# LM5177_PINOUT.net
KiCad netlist of a schematic drawn in Altium Designer
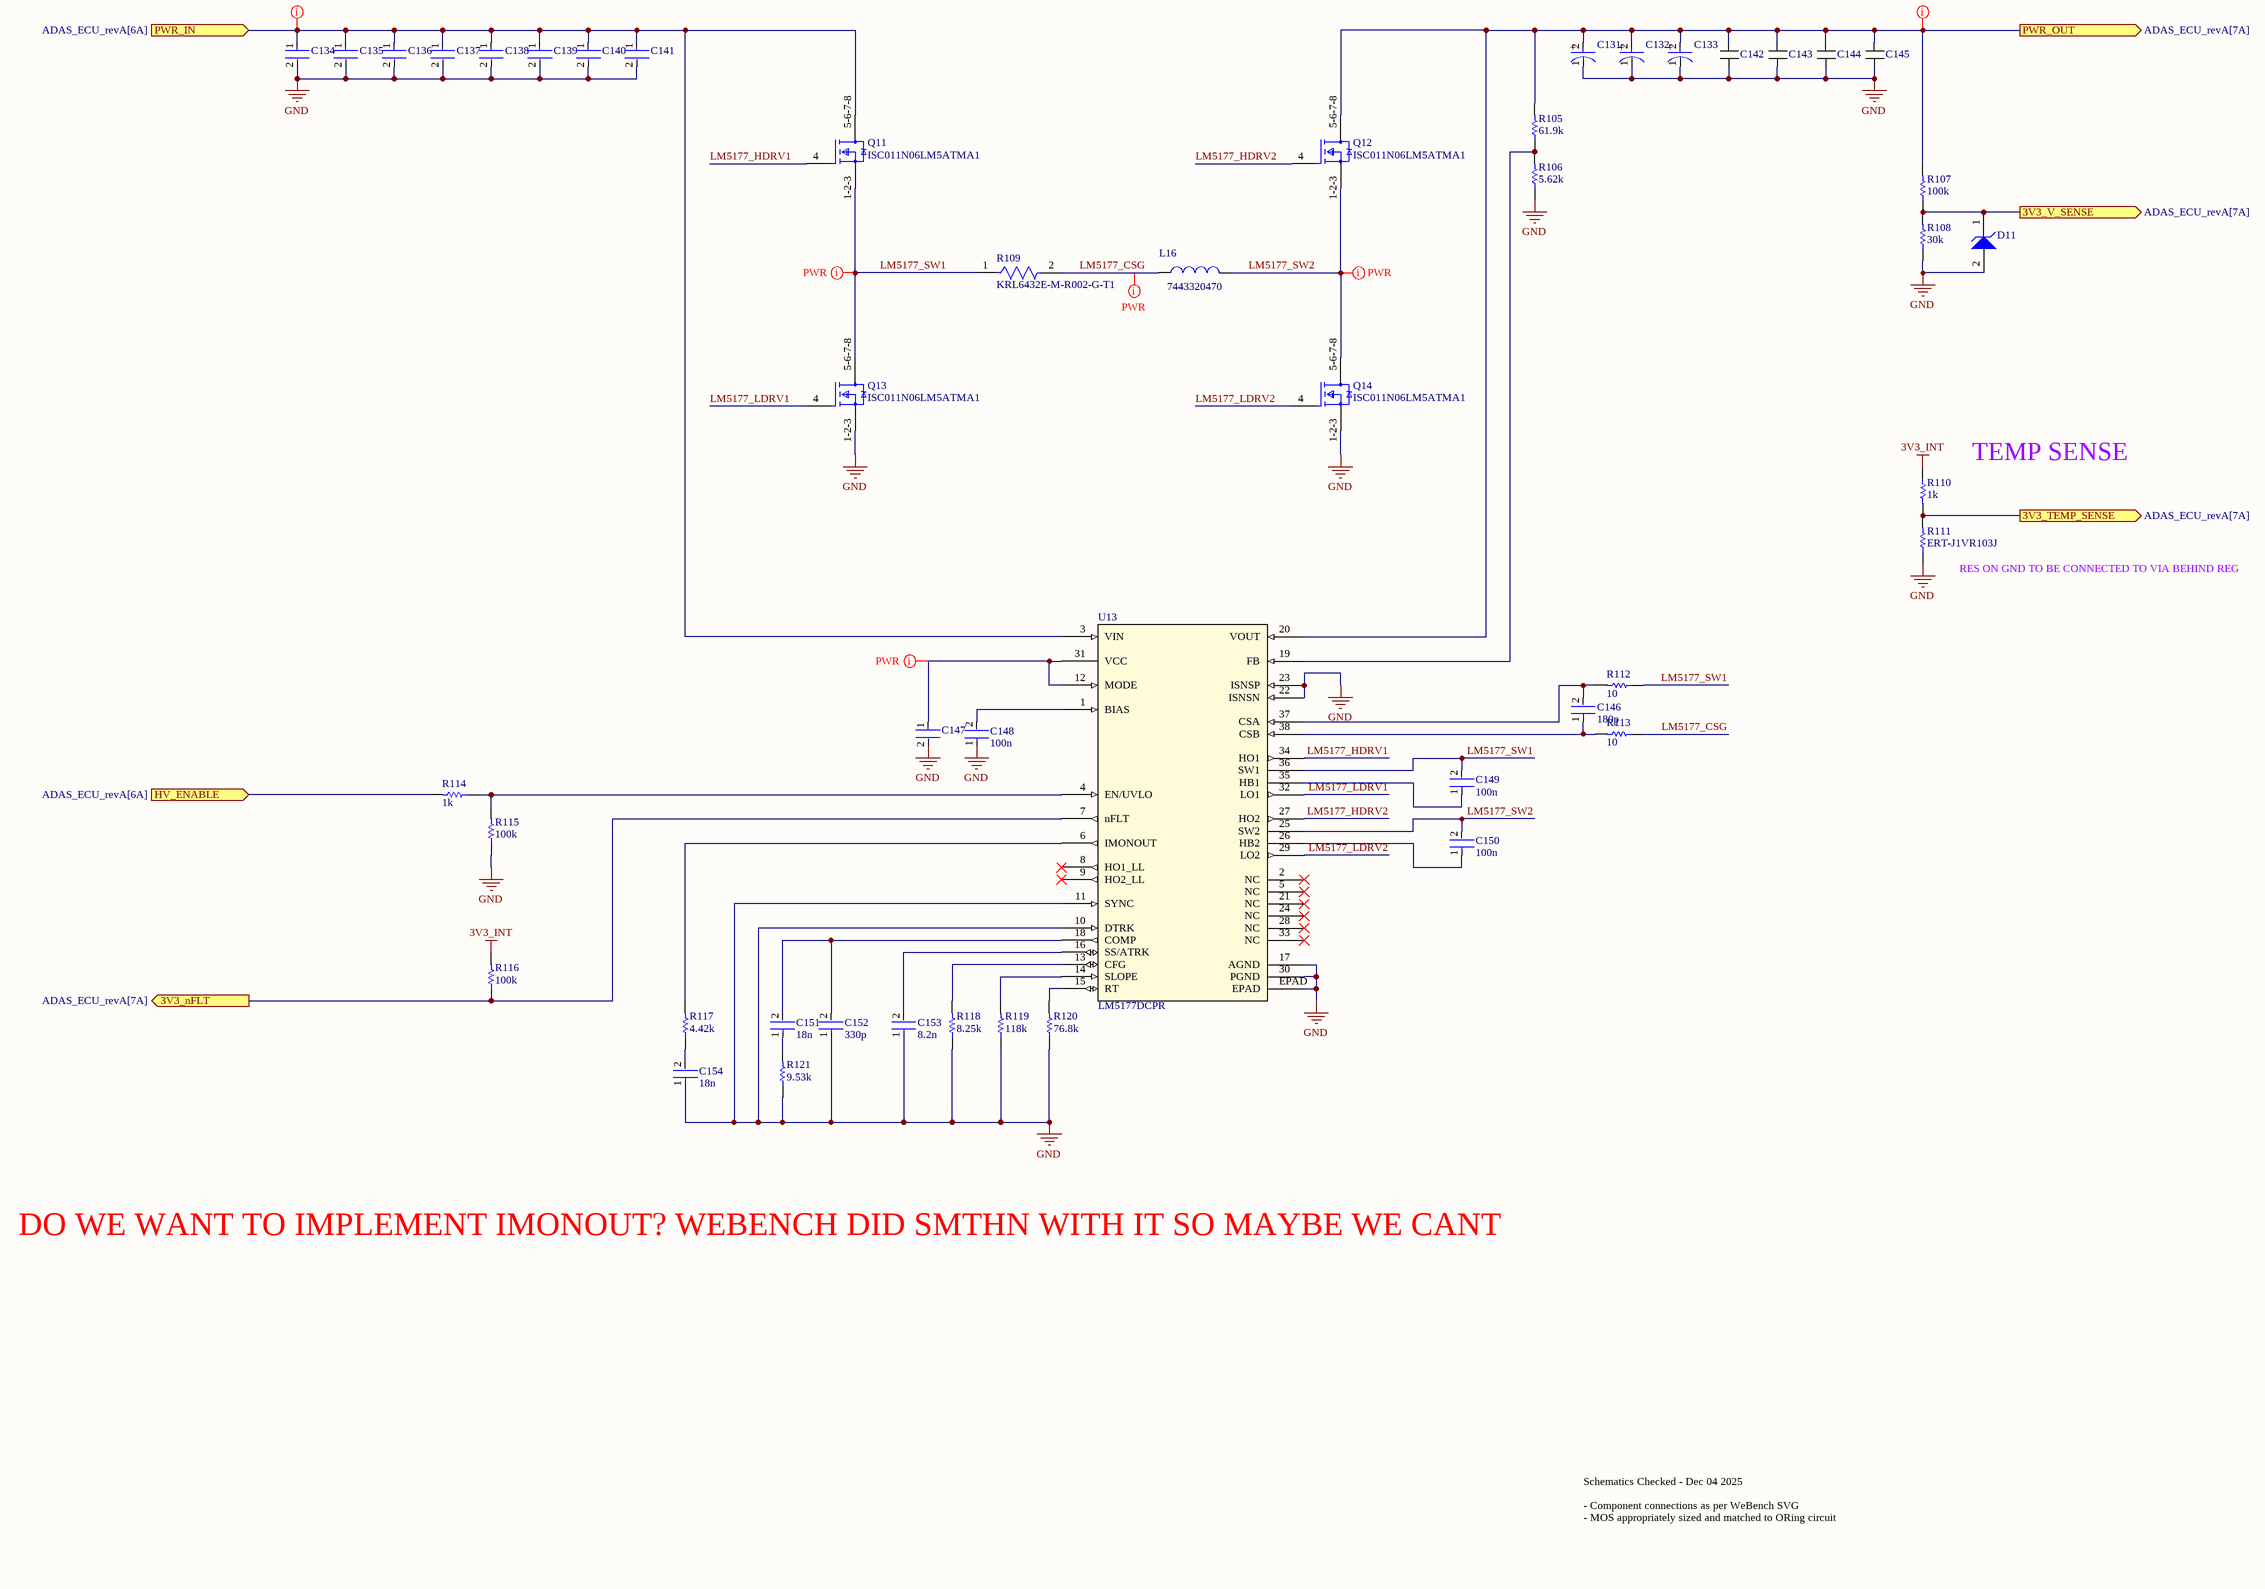
[diagram p0: LM5177_PINOUT.SchDoc]

(export (version "E")
  (design (tool "Eeschema 10.0.6"))
  (components
    (comp (ref "C131")
      (value "20SVPF120M")
      (footprint "FP-OS-CON-SMT-C6-MFG")
      (description "Conductive Polymer Aluminum Solid Capacitors (OS-CON) 120uF ±20% 20V")
      (fields (field (name "TOLERANCE") "20%") (field (name "VOLTAGE") "20V"))
      (libsource (lib "Altium Content Vault") (part "a00bbbee19879c290e62620ae7e47b1"))
    )
    (comp (ref "C132")
      (value "20SVPF120M")
      (footprint "FP-OS-CON-SMT-C6-MFG")
      (description "Conductive Polymer Aluminum Solid Capacitors (OS-CON) 120uF ±20% 20V")
      (fields (field (name "TOLERANCE") "20%") (field (name "VOLTAGE") "20V"))
      (libsource (lib "Altium Content Vault") (part "a00bbbee19879c290e62620ae7e47b1"))
    )
    (comp (ref "C133")
      (value "20SVPF120M")
      (footprint "FP-OS-CON-SMT-C6-MFG")
      (description "Conductive Polymer Aluminum Solid Capacitors (OS-CON) 120uF ±20% 20V")
      (fields (field (name "TOLERANCE") "20%") (field (name "VOLTAGE") "20V"))
      (libsource (lib "Altium Content Vault") (part "a00bbbee19879c290e62620ae7e47b1"))
    )
    (comp (ref "C134")
      (value "C3225X7R1H106M250AC")
      (footprint "FP-C3225-250-0_4-MFG")
      (description "Multilayer Ceramic Capacitors 10uF ±20% 50V X7R SMD 1210")
      (fields (field (name "TOLERANCE") "20%"))
      (libsource (lib "Altium Content Vault") (part "02cd4be3c70576c341d710602a673aa"))
    )
    (comp (ref "C135")
      (value "C3225X7R1H106M250AC")
      (footprint "FP-C3225-250-0_4-MFG")
      (description "Multilayer Ceramic Capacitors 10uF ±20% 50V X7R SMD 1210")
      (fields (field (name "TOLERANCE") "20%"))
      (libsource (lib "Altium Content Vault") (part "02cd4be3c70576c341d710602a673aa"))
    )
    (comp (ref "C136")
      (value "C3225X7R1H106M250AC")
      (footprint "FP-C3225-250-0_4-MFG")
      (description "Multilayer Ceramic Capacitors 10uF ±20% 50V X7R SMD 1210")
      (fields (field (name "TOLERANCE") "20%"))
      (libsource (lib "Altium Content Vault") (part "02cd4be3c70576c341d710602a673aa"))
    )
    (comp (ref "C137")
      (value "C3225X7R1H106M250AC")
      (footprint "FP-C3225-250-0_4-MFG")
      (description "Multilayer Ceramic Capacitors 10uF ±20% 50V X7R SMD 1210")
      (fields (field (name "TOLERANCE") "20%"))
      (libsource (lib "Altium Content Vault") (part "02cd4be3c70576c341d710602a673aa"))
    )
    (comp (ref "C138")
      (value "C3225X7R1H106M250AC")
      (footprint "FP-C3225-250-0_4-MFG")
      (description "Multilayer Ceramic Capacitors 10uF ±20% 50V X7R SMD 1210")
      (fields (field (name "TOLERANCE") "20%"))
      (libsource (lib "Altium Content Vault") (part "02cd4be3c70576c341d710602a673aa"))
    )
    (comp (ref "C139")
      (value "C3225X7R1H106M250AC")
      (footprint "FP-C3225-250-0_4-MFG")
      (description "Multilayer Ceramic Capacitors 10uF ±20% 50V X7R SMD 1210")
      (fields (field (name "TOLERANCE") "20%"))
      (libsource (lib "Altium Content Vault") (part "02cd4be3c70576c341d710602a673aa"))
    )
    (comp (ref "C140")
      (value "C3225X7R1H106M250AC")
      (footprint "FP-C3225-250-0_4-MFG")
      (description "Multilayer Ceramic Capacitors 10uF ±20% 50V X7R SMD 1210")
      (fields (field (name "TOLERANCE") "20%"))
      (libsource (lib "Altium Content Vault") (part "02cd4be3c70576c341d710602a673aa"))
    )
    (comp (ref "C141")
      (value "C3225X7R1H106M250AC")
      (footprint "FP-C3225-250-0_4-MFG")
      (description "Multilayer Ceramic Capacitors 10uF ±20% 50V X7R SMD 1210")
      (fields (field (name "TOLERANCE") "20%"))
      (libsource (lib "Altium Content Vault") (part "02cd4be3c70576c341d710602a673aa"))
    )
    (comp (ref "C142")
      (value "CGA9P2X7R1E226M250KA")
      (footprint "CGA9P2X7R1E226M250KA-Footprint-1")
      (description "25V 22uF X7R 卤20% 2220 Multilayer Ceramic Capacitors MLCC - SMD/SMT ROHS")
      (fields (field (name "TOLERANCE") "20%"))
      (libsource (lib "Space Concordia") (part "CGA9P2X7R1E226M250KA"))
    )
    (comp (ref "C143")
      (value "CGA9P2X7R1E226M250KA")
      (footprint "CGA9P2X7R1E226M250KA-Footprint-1")
      (description "25V 22uF X7R 卤20% 2220 Multilayer Ceramic Capacitors MLCC - SMD/SMT ROHS")
      (fields (field (name "TOLERANCE") "20%"))
      (libsource (lib "Space Concordia") (part "CGA9P2X7R1E226M250KA"))
    )
    (comp (ref "C144")
      (value "CGA9P2X7R1E226M250KA")
      (footprint "CGA9P2X7R1E226M250KA-Footprint-1")
      (description "25V 22uF X7R 卤20% 2220 Multilayer Ceramic Capacitors MLCC - SMD/SMT ROHS")
      (fields (field (name "TOLERANCE") "20%"))
      (libsource (lib "Space Concordia") (part "CGA9P2X7R1E226M250KA"))
    )
    (comp (ref "C145")
      (value "CGA9P2X7R1E226M250KA")
      (footprint "CGA9P2X7R1E226M250KA-Footprint-1")
      (description "25V 22uF X7R 卤20% 2220 Multilayer Ceramic Capacitors MLCC - SMD/SMT ROHS")
      (fields (field (name "TOLERANCE") "20%"))
      (libsource (lib "Space Concordia") (part "CGA9P2X7R1E226M250KA"))
    )
    (comp (ref "C146")
      (value "180p")
      (footprint "FP-0402-L_1_0_0_05-W_0_5-IPC_A")
      (description "LARGE PADS, 0402 CAP, CHANGE COMMENT TO MATCH REAL P/N")
      (libsource (lib "Space Concordia") (part "b4654b650e69147ec39a6b967a45e02"))
    )
    (comp (ref "C147")
      (value "GRM188R60J226MEA0D")
      (footprint "FP-GRM188-0_1-e0_2_0_5-MFG")
      (description "22uF cap, diff pn")
      (fields (field (name "VOLTAGE") "10V") (field (name "TOLERANCE") "10%"))
      (libsource (lib "Altium Content Vault") (part "11868f565c42a9108669ba33697ecf6"))
    )
    (comp (ref "C148")
      (value "100n")
      (footprint "FP-0402-L_1_0_0_05-W_0_5-IPC_A")
      (description "LARGE PADS, 0402 CAP, CHANGE COMMENT TO MATCH REAL P/N")
      (libsource (lib "Space Concordia") (part "b4654b650e69147ec39a6b967a45e02"))
    )
    (comp (ref "C149")
      (value "100n")
      (footprint "FP-0402-L_1_0_0_05-W_0_5-IPC_A")
      (description "LARGE PADS, 0402 CAP, CHANGE COMMENT TO MATCH REAL P/N")
      (libsource (lib "Space Concordia") (part "b4654b650e69147ec39a6b967a45e02"))
    )
    (comp (ref "C150")
      (value "100n")
      (footprint "FP-0402-L_1_0_0_05-W_0_5-IPC_A")
      (description "LARGE PADS, 0402 CAP, CHANGE COMMENT TO MATCH REAL P/N")
      (libsource (lib "Space Concordia") (part "b4654b650e69147ec39a6b967a45e02"))
    )
    (comp (ref "C151")
      (value "18n")
      (footprint "FP-0402-L_1_0_0_05-W_0_5-IPC_A")
      (description "LARGE PADS, 0402 CAP, CHANGE COMMENT TO MATCH REAL P/N")
      (libsource (lib "Space Concordia") (part "b4654b650e69147ec39a6b967a45e02"))
    )
    (comp (ref "C152")
      (value "330p")
      (footprint "FP-0402-L_1_0_0_05-W_0_5-IPC_A")
      (description "LARGE PADS, 0402 CAP, CHANGE COMMENT TO MATCH REAL P/N")
      (libsource (lib "Space Concordia") (part "b4654b650e69147ec39a6b967a45e02"))
    )
    (comp (ref "C153")
      (value "8.2n")
      (footprint "FP-0402-L_1_0_0_05-W_0_5-IPC_A")
      (description "LARGE PADS, 0402 CAP, CHANGE COMMENT TO MATCH REAL P/N")
      (libsource (lib "Space Concordia") (part "b4654b650e69147ec39a6b967a45e02"))
    )
    (comp (ref "C154")
      (value "18n")
      (footprint "FP-0402-L_1_0_0_05-W_0_5-IPC_A")
      (description "LARGE PADS, 0402 CAP, CHANGE COMMENT TO MATCH REAL P/N")
      (libsource (lib "Space Concordia") (part "b4654b650e69147ec39a6b967a45e02"))
    )
    (comp (ref "D11")
      (value "MM5Z3V3T1G")
      (footprint "ONSC-SOD-523-2-502-01_V")
      (description "Zener Voltage Regulator, 500 mW, 2-Pin SOD-523, Pb-Free, Tape and Reel")
      (fields (field (name "MANUFACTURER") "On Semiconductor"))
      (libsource (lib "Altium Content Vault") (part "ONSC-K1A2-2"))
    )
    (comp (ref "L16")
      (value "7443320470")
      (footprint "WE-HCC_1210")
      (description "We-hcc Series, Shielded Wire-wound SMD Inductor With Ferrite Core, 4.7 Uh")
      (libsource (lib "Altium Content Vault") (part "Inductor - 1"))
    )
    (comp (ref "Q11")
      (value "ISC011N06LM5ATMA1")
      (footprint "FP-PG-TDSON-8-MFG")
      (description "TRENCH 40<-<100V PG-TDSON-8")
      (libsource (lib "Altium Content Vault") (part "3085234d4498bcd04bc7e5400bb7c96"))
    )
    (comp (ref "Q12")
      (value "ISC011N06LM5ATMA1")
      (footprint "FP-PG-TDSON-8-MFG")
      (description "TRENCH 40<-<100V PG-TDSON-8")
      (libsource (lib "Altium Content Vault") (part "3085234d4498bcd04bc7e5400bb7c96"))
    )
    (comp (ref "Q13")
      (value "ISC011N06LM5ATMA1")
      (footprint "FP-PG-TDSON-8-MFG")
      (description "TRENCH 40<-<100V PG-TDSON-8")
      (libsource (lib "Altium Content Vault") (part "3085234d4498bcd04bc7e5400bb7c96"))
    )
    (comp (ref "Q14")
      (value "ISC011N06LM5ATMA1")
      (footprint "FP-PG-TDSON-8-MFG")
      (description "TRENCH 40<-<100V PG-TDSON-8")
      (libsource (lib "Altium Content Vault") (part "3085234d4498bcd04bc7e5400bb7c96"))
    )
    (comp (ref "R105")
      (value "61.9k")
      (footprint "R0603B")
      (description "Resistor")
      (libsource (lib "Space Concordia") (part "Resistor"))
    )
    (comp (ref "R106")
      (value "5.62k")
      (footprint "R0603B")
      (description "Resistor")
      (libsource (lib "Space Concordia") (part "Resistor"))
    )
    (comp (ref "R107")
      (value "100k")
      (footprint "R0603B")
      (description "Resistor")
      (libsource (lib "Space Concordia") (part "Resistor"))
    )
    (comp (ref "R108")
      (value "30k")
      (footprint "R0603B")
      (description "Resistor")
      (libsource (lib "Space Concordia") (part "Resistor"))
    )
    (comp (ref "R109")
      (value "KRL6432E-M-R002-G-T1")
      (footprint "FP-KRL6432E-MFG")
      (description "KRL6432E-M-R002-G-T1 Metal Foil Low Resistance Chip Resistor (long-side terminal), 2512, RoHS")
      (fields (field (name "TOLERANCE") "2%"))
      (libsource (lib "Altium Content Vault") (part "1029c3af85768c4190bb7ad29bc67b5"))
    )
    (comp (ref "R110")
      (value "1k")
      (footprint "R0603B")
      (description "Resistor")
      (libsource (lib "Space Concordia") (part "Resistor"))
    )
    (comp (ref "R111")
      (value "ERT-J1VR103J")
      (footprint "RESC1608X90X30ML15T20")
      (fields (field (name "MANUFACTURER") "Panasonic"))
      (libsource (lib "Altium Content Vault") (part "RES"))
    )
    (comp (ref "R112")
      (value "10")
      (footprint "R0603B")
      (description "Resistor")
      (libsource (lib "Space Concordia") (part "Resistor"))
    )
    (comp (ref "R113")
      (value "10")
      (footprint "R0603B")
      (description "Resistor")
      (libsource (lib "Space Concordia") (part "Resistor"))
    )
    (comp (ref "R114")
      (value "1k")
      (footprint "R0603B")
      (description "Resistor")
      (libsource (lib "Space Concordia") (part "Resistor"))
    )
    (comp (ref "R115")
      (value "100k")
      (footprint "R0603B")
      (description "Resistor")
      (libsource (lib "Space Concordia") (part "Resistor"))
    )
    (comp (ref "R116")
      (value "100k")
      (footprint "R0603B")
      (description "Resistor")
      (libsource (lib "Space Concordia") (part "Resistor"))
    )
    (comp (ref "R117")
      (value "4.42k")
      (footprint "R0603B")
      (description "Resistor")
      (libsource (lib "Space Concordia") (part "Resistor"))
    )
    (comp (ref "R118")
      (value "8.25k")
      (footprint "R0603B")
      (description "Resistor")
      (libsource (lib "Space Concordia") (part "Resistor"))
    )
    (comp (ref "R119")
      (value "118k")
      (footprint "R0603B")
      (description "Resistor")
      (libsource (lib "Space Concordia") (part "Resistor"))
    )
    (comp (ref "R120")
      (value "76.8k")
      (footprint "R0603B")
      (description "Resistor")
      (libsource (lib "Space Concordia") (part "Resistor"))
    )
    (comp (ref "R121")
      (value "9.53k")
      (footprint "R0603B")
      (description "Resistor")
      (libsource (lib "Space Concordia") (part "Resistor"))
    )
    (comp (ref "U13")
      (value "LM5177DCPR")
      (footprint "LM5177DCPR-Footprint-1")
      (description "IC Buck-Boost Regulator Positive Output Step-Up/Step-Down DC-DC Controller IC 38-HTSSOP")
      (libsource (lib "Space Concordia") (part "LM5177DCPR"))
    )
  )
  (nets
    (net (code "1") (name "/3V3_TEMP_SENSE") (class "Default")
      (node (ref "R110") (pin "2") (pinfunction "2_2") (pintype "passive"))
      (node (ref "R111") (pin "2") (pinfunction "2_2") (pintype "passive"))
    )
    (net (code "2") (name "/3V3_V_SENSE") (class "Default")
      (node (ref "D11") (pin "1") (pinfunction "K_1") (pintype "passive"))
      (node (ref "R107") (pin "1") (pinfunction "1_1") (pintype "passive"))
      (node (ref "R108") (pin "2") (pinfunction "2_2") (pintype "passive"))
    )
    (net (code "3") (name "/3V3_nFLT") (class "Default")
      (node (ref "R116") (pin "1") (pinfunction "1_1") (pintype "passive"))
      (node (ref "U13") (pin "7") (pinfunction "nFLT_7") (pintype "output"))
    )
    (net (code "4") (name "/HV_ENABLE") (class "Default")
      (node (ref "R114") (pin "2") (pinfunction "2_2") (pintype "passive"))
    )
    (net (code "5") (name "/LM5177_CSG") (class "Default")
      (node (ref "L16") (pin "1") (pinfunction "1_1") (pintype "passive"))
      (node (ref "R109") (pin "2") (pinfunction "2_2") (pintype "passive"))
      (node (ref "R113") (pin "1") (pinfunction "1_1") (pintype "passive"))
    )
    (net (code "6") (name "/LM5177_HDRV1") (class "Default")
      (node (ref "Q11") (pin "4") (pinfunction "G_4") (pintype "passive"))
      (node (ref "U13") (pin "34") (pinfunction "HO1_34") (pintype "output"))
    )
    (net (code "7") (name "/LM5177_HDRV2") (class "Default")
      (node (ref "Q12") (pin "4") (pinfunction "G_4") (pintype "passive"))
      (node (ref "U13") (pin "27") (pinfunction "HO2_27") (pintype "output"))
    )
    (net (code "8") (name "/LM5177_LDRV1") (class "Default")
      (node (ref "Q13") (pin "4") (pinfunction "G_4") (pintype "passive"))
      (node (ref "U13") (pin "32") (pinfunction "LO1_32") (pintype "output"))
    )
    (net (code "9") (name "/LM5177_LDRV2") (class "Default")
      (node (ref "Q14") (pin "4") (pinfunction "G_4") (pintype "passive"))
      (node (ref "U13") (pin "29") (pinfunction "LO2_29") (pintype "output"))
    )
    (net (code "10") (name "/LM5177_SW1") (class "Default")
      (node (ref "C149") (pin "2") (pinfunction "2_2") (pintype "passive"))
      (node (ref "Q11") (pin "1-2-3") (pinfunction "S_1-2-3") (pintype "passive"))
      (node (ref "Q13") (pin "5-6-7-8") (pinfunction "D_5-6-7-8") (pintype "passive"))
      (node (ref "R109") (pin "1") (pinfunction "1_1") (pintype "passive"))
      (node (ref "R112") (pin "1") (pinfunction "1_1") (pintype "passive"))
      (node (ref "U13") (pin "36") (pinfunction "SW1_36") (pintype "power_in"))
    )
    (net (code "11") (name "/LM5177_SW2") (class "Default")
      (node (ref "C150") (pin "2") (pinfunction "2_2") (pintype "passive"))
      (node (ref "L16") (pin "2") (pinfunction "2_2") (pintype "passive"))
      (node (ref "Q12") (pin "1-2-3") (pinfunction "S_1-2-3") (pintype "passive"))
      (node (ref "Q14") (pin "5-6-7-8") (pinfunction "D_5-6-7-8") (pintype "passive"))
      (node (ref "U13") (pin "25") (pinfunction "SW2_25") (pintype "power_in"))
    )
    (net (code "12") (name "/PWR_IN") (class "Default")
      (node (ref "C134") (pin "1") (pinfunction "1_1") (pintype "passive"))
      (node (ref "C135") (pin "1") (pinfunction "1_1") (pintype "passive"))
      (node (ref "C136") (pin "1") (pinfunction "1_1") (pintype "passive"))
      (node (ref "C137") (pin "1") (pinfunction "1_1") (pintype "passive"))
      (node (ref "C138") (pin "1") (pinfunction "1_1") (pintype "passive"))
      (node (ref "C139") (pin "1") (pinfunction "1_1") (pintype "passive"))
      (node (ref "C140") (pin "1") (pinfunction "1_1") (pintype "passive"))
      (node (ref "C141") (pin "1") (pinfunction "1_1") (pintype "passive"))
      (node (ref "Q11") (pin "5-6-7-8") (pinfunction "D_5-6-7-8") (pintype "passive"))
      (node (ref "U13") (pin "3") (pinfunction "VIN_3") (pintype "input"))
    )
    (net (code "13") (name "/PWR_OUT") (class "Default")
      (node (ref "C131") (pin "2") (pinfunction "A_2") (pintype "passive"))
      (node (ref "C132") (pin "2") (pinfunction "A_2") (pintype "passive"))
      (node (ref "C133") (pin "2") (pinfunction "A_2") (pintype "passive"))
      (node (ref "C142") (pin "1") (pinfunction "1_1") (pintype "passive"))
      (node (ref "C143") (pin "1") (pinfunction "1_1") (pintype "passive"))
      (node (ref "C144") (pin "1") (pinfunction "1_1") (pintype "passive"))
      (node (ref "C145") (pin "1") (pinfunction "1_1") (pintype "passive"))
      (node (ref "Q12") (pin "5-6-7-8") (pinfunction "D_5-6-7-8") (pintype "passive"))
      (node (ref "R105") (pin "2") (pinfunction "2_2") (pintype "passive"))
      (node (ref "R107") (pin "2") (pinfunction "2_2") (pintype "passive"))
      (node (ref "U13") (pin "20") (pinfunction "VOUT_20") (pintype "input"))
    )
    (net (code "14") (name "3V3_INT") (class "Default")
      (node (ref "R110") (pin "1") (pinfunction "1_1") (pintype "passive"))
      (node (ref "R116") (pin "2") (pinfunction "2_2") (pintype "passive"))
    )
    (net (code "15") (name "GND") (class "Default")
      (node (ref "C131") (pin "1") (pinfunction "C_1") (pintype "passive"))
      (node (ref "C132") (pin "1") (pinfunction "C_1") (pintype "passive"))
      (node (ref "C133") (pin "1") (pinfunction "C_1") (pintype "passive"))
      (node (ref "C134") (pin "2") (pinfunction "2_2") (pintype "passive"))
      (node (ref "C135") (pin "2") (pinfunction "2_2") (pintype "passive"))
      (node (ref "C136") (pin "2") (pinfunction "2_2") (pintype "passive"))
      (node (ref "C137") (pin "2") (pinfunction "2_2") (pintype "passive"))
      (node (ref "C138") (pin "2") (pinfunction "2_2") (pintype "passive"))
      (node (ref "C139") (pin "2") (pinfunction "2_2") (pintype "passive"))
      (node (ref "C140") (pin "2") (pinfunction "2_2") (pintype "passive"))
      (node (ref "C141") (pin "2") (pinfunction "2_2") (pintype "passive"))
      (node (ref "C142") (pin "2") (pinfunction "2_2") (pintype "passive"))
      (node (ref "C143") (pin "2") (pinfunction "2_2") (pintype "passive"))
      (node (ref "C144") (pin "2") (pinfunction "2_2") (pintype "passive"))
      (node (ref "C145") (pin "2") (pinfunction "2_2") (pintype "passive"))
      (node (ref "C147") (pin "2") (pinfunction "2_2") (pintype "passive"))
      (node (ref "C148") (pin "1") (pinfunction "1_1") (pintype "passive"))
      (node (ref "C152") (pin "1") (pinfunction "1_1") (pintype "passive"))
      (node (ref "C153") (pin "1") (pinfunction "1_1") (pintype "passive"))
      (node (ref "C154") (pin "1") (pinfunction "1_1") (pintype "passive"))
      (node (ref "D11") (pin "2") (pinfunction "A_2") (pintype "passive"))
      (node (ref "Q13") (pin "1-2-3") (pinfunction "S_1-2-3") (pintype "passive"))
      (node (ref "Q14") (pin "1-2-3") (pinfunction "S_1-2-3") (pintype "passive"))
      (node (ref "R106") (pin "1") (pinfunction "1_1") (pintype "passive"))
      (node (ref "R108") (pin "1") (pinfunction "1_1") (pintype "passive"))
      (node (ref "R111") (pin "1") (pinfunction "1_1") (pintype "passive"))
      (node (ref "R115") (pin "1") (pinfunction "1_1") (pintype "passive"))
      (node (ref "R118") (pin "1") (pinfunction "1_1") (pintype "passive"))
      (node (ref "R119") (pin "1") (pinfunction "1_1") (pintype "passive"))
      (node (ref "R120") (pin "1") (pinfunction "1_1") (pintype "passive"))
      (node (ref "R121") (pin "1") (pinfunction "1_1") (pintype "passive"))
      (node (ref "U13") (pin "10") (pinfunction "DTRK_10") (pintype "input"))
      (node (ref "U13") (pin "11") (pinfunction "SYNC_11") (pintype "input"))
      (node (ref "U13") (pin "17") (pinfunction "AGND_17") (pintype "power_in"))
      (node (ref "U13") (pin "22") (pinfunction "ISNSN_22") (pintype "input"))
      (node (ref "U13") (pin "23") (pinfunction "ISNSP_23") (pintype "input"))
      (node (ref "U13") (pin "30") (pinfunction "PGND_30") (pintype "power_in"))
      (node (ref "U13") (pin "EPAD") (pinfunction "EPAD_EPAD") (pintype "power_in"))
    )
    (net (code "16") (name "Net-(C151-Pad1)") (class "Default")
      (node (ref "C151") (pin "1") (pinfunction "1_1") (pintype "passive"))
      (node (ref "R121") (pin "2") (pinfunction "2_2") (pintype "passive"))
    )
    (net (code "17") (name "Net-(C154-Pad2)") (class "Default")
      (node (ref "C154") (pin "2") (pinfunction "2_2") (pintype "passive"))
      (node (ref "R117") (pin "1") (pinfunction "1_1") (pintype "passive"))
    )
    (net (code "18") (name "Net-(U13-BIAS)") (class "Default")
      (node (ref "C148") (pin "2") (pinfunction "2_2") (pintype "passive"))
      (node (ref "U13") (pin "1") (pinfunction "BIAS_1") (pintype "input"))
    )
    (net (code "19") (name "Net-(U13-CFG)") (class "Default")
      (node (ref "R118") (pin "2") (pinfunction "2_2") (pintype "passive"))
      (node (ref "U13") (pin "13") (pinfunction "CFG_13") (pintype "bidirectional"))
    )
    (net (code "20") (name "Net-(U13-COMP)") (class "Default")
      (node (ref "C151") (pin "2") (pinfunction "2_2") (pintype "passive"))
      (node (ref "C152") (pin "2") (pinfunction "2_2") (pintype "passive"))
      (node (ref "U13") (pin "18") (pinfunction "COMP_18") (pintype "output"))
    )
    (net (code "21") (name "Net-(U13-CSA)") (class "Default")
      (node (ref "C146") (pin "2") (pinfunction "2_2") (pintype "passive"))
      (node (ref "R112") (pin "2") (pinfunction "2_2") (pintype "passive"))
      (node (ref "U13") (pin "37") (pinfunction "CSA_37") (pintype "input"))
    )
    (net (code "22") (name "Net-(U13-CSB)") (class "Default")
      (node (ref "C146") (pin "1") (pinfunction "1_1") (pintype "passive"))
      (node (ref "R113") (pin "2") (pinfunction "2_2") (pintype "passive"))
      (node (ref "U13") (pin "38") (pinfunction "CSB_38") (pintype "input"))
    )
    (net (code "23") (name "Net-(U13-EN{slash}UVLO)") (class "Default")
      (node (ref "R114") (pin "1") (pinfunction "1_1") (pintype "passive"))
      (node (ref "R115") (pin "2") (pinfunction "2_2") (pintype "passive"))
      (node (ref "U13") (pin "4") (pinfunction "EN/UVLO_4") (pintype "input"))
    )
    (net (code "24") (name "Net-(U13-FB)") (class "Default")
      (node (ref "R105") (pin "1") (pinfunction "1_1") (pintype "passive"))
      (node (ref "R106") (pin "2") (pinfunction "2_2") (pintype "passive"))
      (node (ref "U13") (pin "19") (pinfunction "FB_19") (pintype "input"))
    )
    (net (code "25") (name "Net-(U13-HB1)") (class "Default")
      (node (ref "C149") (pin "1") (pinfunction "1_1") (pintype "passive"))
      (node (ref "U13") (pin "35") (pinfunction "HB1_35") (pintype "power_in"))
    )
    (net (code "26") (name "Net-(U13-HB2)") (class "Default")
      (node (ref "C150") (pin "1") (pinfunction "1_1") (pintype "passive"))
      (node (ref "U13") (pin "26") (pinfunction "HB2_26") (pintype "power_in"))
    )
    (net (code "27") (name "Net-(U13-IMONOUT)") (class "Default")
      (node (ref "R117") (pin "2") (pinfunction "2_2") (pintype "passive"))
      (node (ref "U13") (pin "6") (pinfunction "IMONOUT_6") (pintype "output"))
    )
    (net (code "28") (name "Net-(U13-MODE)") (class "Default")
      (node (ref "C147") (pin "1") (pinfunction "1_1") (pintype "passive"))
      (node (ref "U13") (pin "12") (pinfunction "MODE_12") (pintype "input"))
      (node (ref "U13") (pin "31") (pinfunction "VCC_31") (pintype "power_in"))
    )
    (net (code "29") (name "Net-(U13-RT)") (class "Default")
      (node (ref "R120") (pin "2") (pinfunction "2_2") (pintype "passive"))
      (node (ref "U13") (pin "15") (pinfunction "RT_15") (pintype "bidirectional"))
    )
    (net (code "30") (name "Net-(U13-SLOPE)") (class "Default")
      (node (ref "R119") (pin "2") (pinfunction "2_2") (pintype "passive"))
      (node (ref "U13") (pin "14") (pinfunction "SLOPE_14") (pintype "input"))
    )
    (net (code "31") (name "Net-(U13-SS{slash}ATRK)") (class "Default")
      (node (ref "C153") (pin "2") (pinfunction "2_2") (pintype "passive"))
      (node (ref "U13") (pin "16") (pinfunction "SS/ATRK_16") (pintype "bidirectional"))
    )
    (net (code "32") (name "unconnected-(U13-HO1_LL-Pad8)") (class "Default")
      (node (ref "U13") (pin "8") (pinfunction "HO1_LL_8") (pintype "output+no_connect"))
    )
    (net (code "33") (name "unconnected-(U13-HO2_LL-Pad9)") (class "Default")
      (node (ref "U13") (pin "9") (pinfunction "HO2_LL_9") (pintype "output+no_connect"))
    )
    (net (code "34") (name "unconnected-(U13-NC-Pad2)") (class "Default")
      (node (ref "U13") (pin "2") (pinfunction "NC_2") (pintype "passive+no_connect"))
    )
    (net (code "35") (name "unconnected-(U13-NC-Pad5)") (class "Default")
      (node (ref "U13") (pin "5") (pinfunction "NC_5") (pintype "passive+no_connect"))
    )
    (net (code "36") (name "unconnected-(U13-NC-Pad21)") (class "Default")
      (node (ref "U13") (pin "21") (pinfunction "NC_21") (pintype "passive+no_connect"))
    )
    (net (code "37") (name "unconnected-(U13-NC-Pad24)") (class "Default")
      (node (ref "U13") (pin "24") (pinfunction "NC_24") (pintype "passive+no_connect"))
    )
    (net (code "38") (name "unconnected-(U13-NC-Pad28)") (class "Default")
      (node (ref "U13") (pin "28") (pinfunction "NC_28") (pintype "passive+no_connect"))
    )
    (net (code "39") (name "unconnected-(U13-NC-Pad33)") (class "Default")
      (node (ref "U13") (pin "33") (pinfunction "NC_33") (pintype "passive+no_connect"))
    )
  )
)
